# working.net
KiCad netlist of a schematic drawn in EAGLE
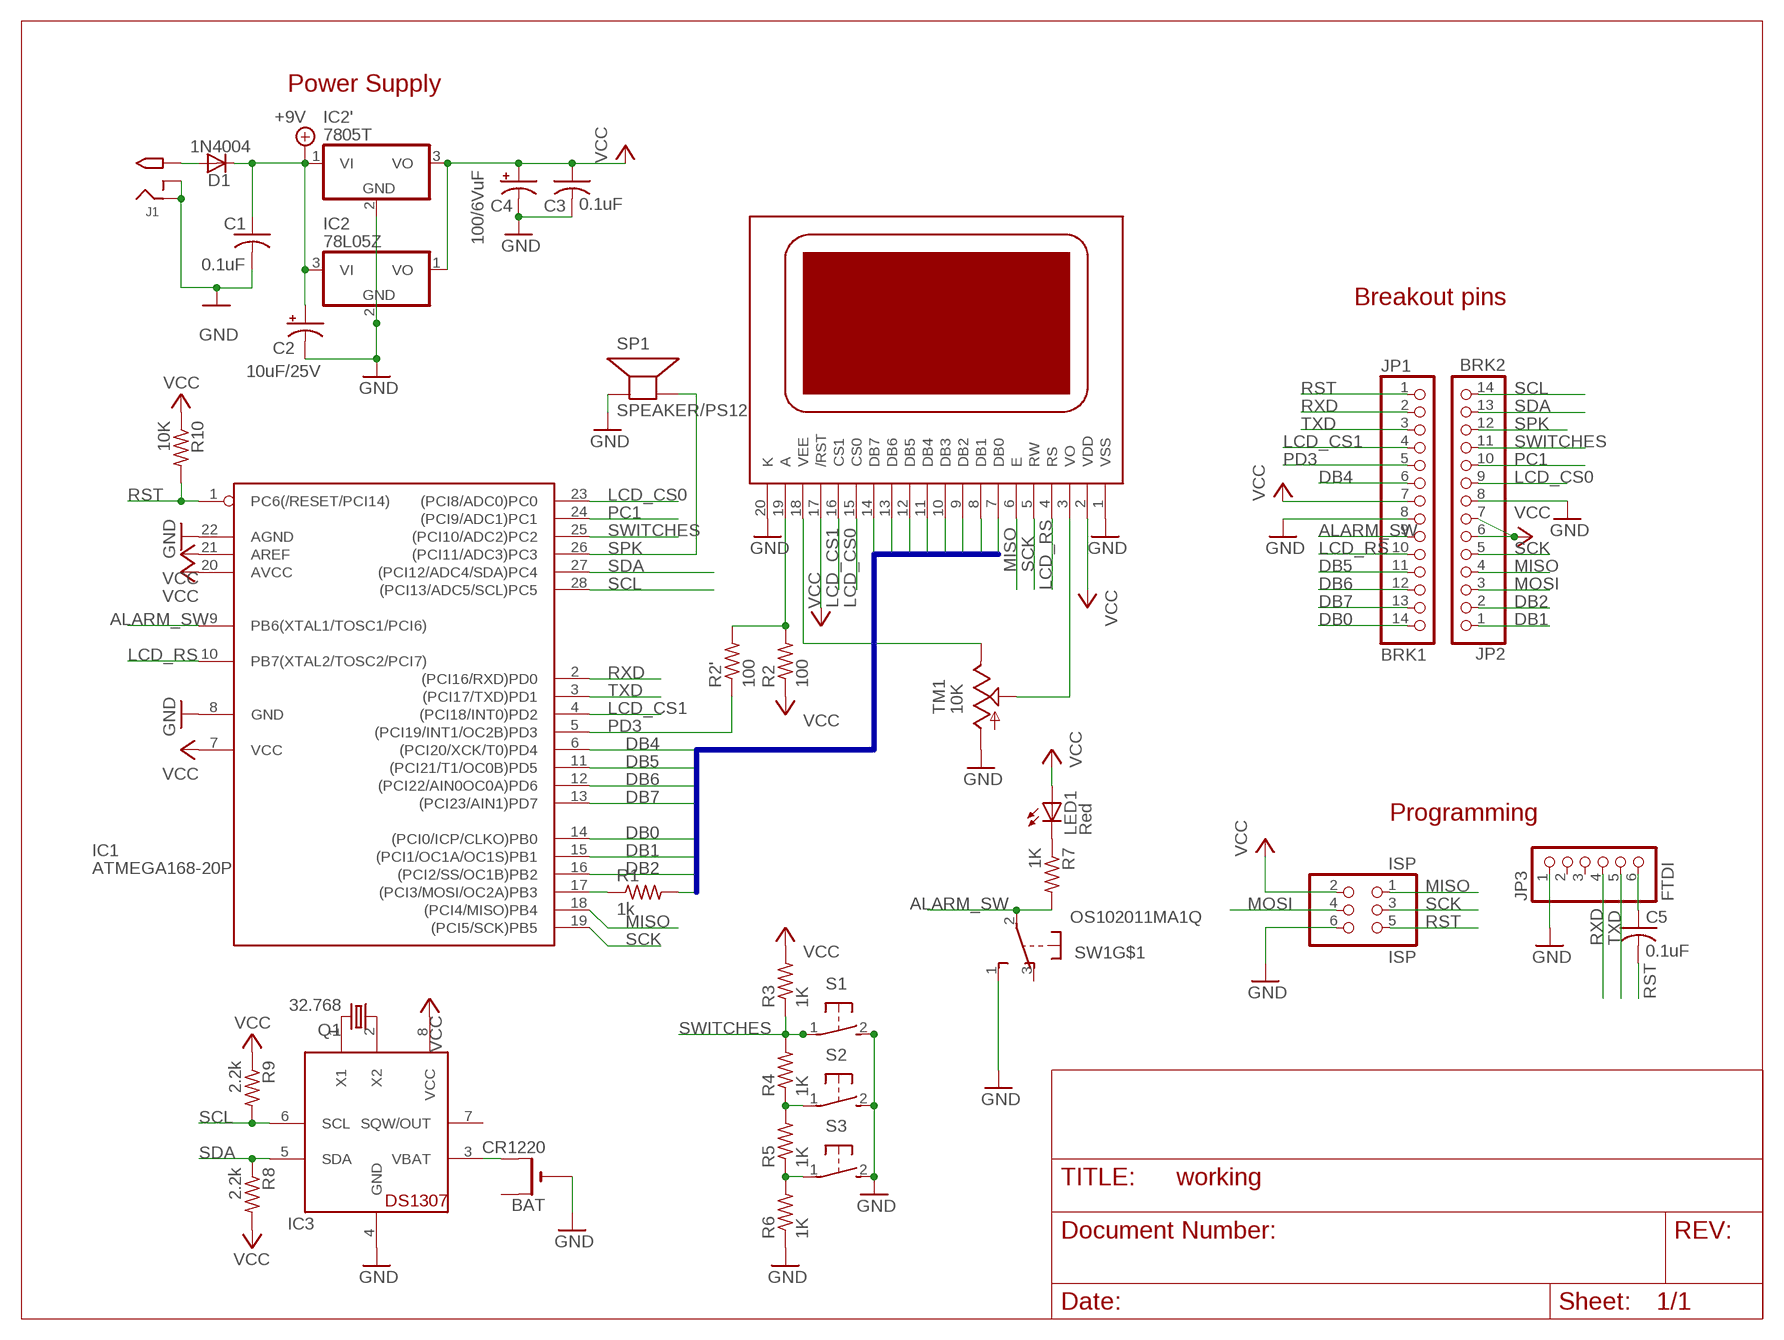
[diagram p0: schematic, sheet 1]

(export (version "E")
  (design (tool "Eeschema 10.0.6"))
  (components
    (comp (ref "BAT")
      (value "CR1220")
      (footprint "eagle-import:CR1220-THM")
      (libsource (lib "eagle-import") (part "CR1220THM"))
    )
    (comp (ref "C1")
      (value "0.1uF")
      (footprint "eagle-import:C025-025X050")
      (libsource (lib "eagle-import") (part "C-US025-025X050"))
    )
    (comp (ref "C2")
      (value "10uF/25V")
      (footprint "eagle-import:E2,5-6E")
      (libsource (lib "eagle-import") (part "CPOL-USE2,5-6E"))
    )
    (comp (ref "C3")
      (value "0.1uF")
      (footprint "eagle-import:C025-025X050")
      (libsource (lib "eagle-import") (part "C-US025-025X050"))
    )
    (comp (ref "C4")
      (value "100/6VuF")
      (footprint "eagle-import:E2,5-6E")
      (libsource (lib "eagle-import") (part "CPOL-USE2,5-6E"))
    )
    (comp (ref "C5")
      (value "0.1uF")
      (footprint "eagle-import:C025-025X050")
      (libsource (lib "eagle-import") (part "C-US025-025X050"))
    )
    (comp (ref "D1")
      (value "1N4004")
      (footprint "eagle-import:DO41-10")
      (libsource (lib "eagle-import") (part "1N4004"))
    )
    (comp (ref "IC1")
      (value "ATMEGA168-20P")
      (footprint "eagle-import:DIL28-3")
      (libsource (lib "eagle-import") (part "ATMEGA168P-20"))
    )
    (comp (ref "IC2")
      (value "78L05Z")
      (footprint "eagle-import:TO92")
      (libsource (lib "eagle-import") (part "linear-ez_78ZL05"))
    )
    (comp (ref "IC2'")
      (value "7805T")
      (footprint "eagle-import:TO220H")
      (libsource (lib "eagle-import") (part "78T05"))
    )
    (comp (ref "IC3")
      (value "DS1307")
      (footprint "eagle-import:DIL08")
      (libsource (lib "eagle-import") (part "DS1307"))
    )
    (comp (ref "ISP")
      (value "ISP")
      (footprint "eagle-import:2X03")
      (libsource (lib "eagle-import") (part "PINHD-2X3"))
    )
    (comp (ref "J1")
      (value "2.1MMJACK")
      (footprint "eagle-import:PJ-102A")
      (libsource (lib "eagle-import") (part "2.1MMJACK"))
    )
    (comp (ref "JP1")
      (value "BRK1")
      (footprint "eagle-import:1X14")
      (libsource (lib "eagle-import") (part "PINHD-1X14"))
    )
    (comp (ref "JP2")
      (value "BRK2")
      (footprint "eagle-import:1X14")
      (libsource (lib "eagle-import") (part "PINHD-1X14"))
    )
    (comp (ref "JP3")
      (value "FTDI")
      (footprint "eagle-import:1X06")
      (libsource (lib "eagle-import") (part "PINHD-1X6"))
    )
    (comp (ref "LED1")
      (value "Red")
      (footprint "eagle-import:LED3MM")
      (libsource (lib "eagle-import") (part "LED3MM"))
    )
    (comp (ref "Q1")
      (value "32.768")
      (footprint "eagle-import:TC38H")
      (libsource (lib "eagle-import") (part "CRYTALTC38H"))
    )
    (comp (ref "R1")
      (value "1k")
      (footprint "eagle-import:0207_10")
      (libsource (lib "eagle-import") (part "R-US_0207/10"))
    )
    (comp (ref "R2")
      (value "100")
      (footprint "eagle-import:0207_10")
      (libsource (lib "eagle-import") (part "R-US_0207/10"))
    )
    (comp (ref "R2'")
      (value "100")
      (footprint "eagle-import:0207_10")
      (libsource (lib "eagle-import") (part "R-US_0207/10"))
    )
    (comp (ref "R3")
      (value "1K")
      (footprint "eagle-import:0207_10")
      (libsource (lib "eagle-import") (part "R-US_0207/10"))
    )
    (comp (ref "R4")
      (value "1K")
      (footprint "eagle-import:0207_10")
      (libsource (lib "eagle-import") (part "R-US_0207/10"))
    )
    (comp (ref "R5")
      (value "1K")
      (footprint "eagle-import:0207_10")
      (libsource (lib "eagle-import") (part "R-US_0207/10"))
    )
    (comp (ref "R6")
      (value "1K")
      (footprint "eagle-import:0207_10")
      (libsource (lib "eagle-import") (part "R-US_0207/10"))
    )
    (comp (ref "R7")
      (value "1K")
      (footprint "eagle-import:0207_10")
      (libsource (lib "eagle-import") (part "R-US_0207/10"))
    )
    (comp (ref "R8")
      (value "2.2k")
      (footprint "eagle-import:0207_10")
      (libsource (lib "eagle-import") (part "R-US_0207/10"))
    )
    (comp (ref "R9")
      (value "2.2k")
      (footprint "eagle-import:0207_10")
      (libsource (lib "eagle-import") (part "R-US_0207/10"))
    )
    (comp (ref "R10")
      (value "10K")
      (footprint "eagle-import:0207_10")
      (libsource (lib "eagle-import") (part "R-US_0207/10"))
    )
    (comp (ref "S1")
      (value "31-XX")
      (footprint "eagle-import:B3F-31XX")
      (libsource (lib "eagle-import") (part "31-XX"))
    )
    (comp (ref "S2")
      (value "31-XX")
      (footprint "eagle-import:B3F-31XX")
      (libsource (lib "eagle-import") (part "31-XX"))
    )
    (comp (ref "S3")
      (value "31-XX")
      (footprint "eagle-import:B3F-31XX")
      (libsource (lib "eagle-import") (part "31-XX"))
    )
    (comp (ref "SP1")
      (value "SPEAKER/PS12")
      (footprint "eagle-import:PS12")
      (libsource (lib "eagle-import") (part "SPEAKER/PS12"))
    )
    (comp (ref "SW1")
      (value "OS102011MA1Q")
      (footprint "eagle-import:OS102011MA1Q")
      (libsource (lib "eagle-import") (part "OS102011MA1Q"))
    )
    (comp (ref "TM1")
      (value "10K")
      (footprint "eagle-import:CA6H")
      (libsource (lib "eagle-import") (part "TRIM_US-CA6H"))
    )
    (comp (ref "U$1")
      (value "TS12864A")
      (footprint "eagle-import:TS12864")
      (libsource (lib "eagle-import") (part "TS12864A"))
    )
  )
  (nets
    (net (code "1") (name "+9V") (class "Default")
      (node (ref "C1") (pin "1") (pinfunction "1_1") (pintype "passive"))
      (node (ref "C2") (pin "+") (pinfunction "+_+") (pintype "passive"))
      (node (ref "D1") (pin "C") (pinfunction "C_C") (pintype "passive"))
      (node (ref "IC2") (pin "3") (pinfunction "VI_3") (pintype "input"))
      (node (ref "IC2'") (pin "1") (pinfunction "VI_1") (pintype "input"))
    )
    (net (code "2") (name "/ALARM_SW") (class "Default")
      (node (ref "IC1") (pin "9") (pinfunction "PB6(XTAL1/TOSC1/PCI6)_9") (pintype "bidirectional"))
      (node (ref "JP1") (pin "9") (pinfunction "9_9") (pintype "passive"))
      (node (ref "R7") (pin "2") (pinfunction "2_2") (pintype "passive"))
      (node (ref "SW1") (pin "2") (pinfunction "P_2") (pintype "passive"))
    )
    (net (code "3") (name "/DB0") (class "Default")
      (node (ref "IC1") (pin "14") (pinfunction "(PCI0/ICP/CLKO)PB0_14") (pintype "bidirectional"))
      (node (ref "JP1") (pin "14") (pinfunction "14_14") (pintype "passive"))
      (node (ref "U$1") (pin "7") (pinfunction "DB0_7") (pintype "bidirectional"))
    )
    (net (code "4") (name "/DB1") (class "Default")
      (node (ref "IC1") (pin "15") (pinfunction "(PCI1/OC1A/OC1S)PB1_15") (pintype "bidirectional"))
      (node (ref "JP2") (pin "1") (pinfunction "1_1") (pintype "passive"))
      (node (ref "U$1") (pin "8") (pinfunction "DB1_8") (pintype "bidirectional"))
    )
    (net (code "5") (name "/DB2") (class "Default")
      (node (ref "IC1") (pin "16") (pinfunction "(PCI2/SS/OC1B)PB2_16") (pintype "bidirectional"))
      (node (ref "JP2") (pin "2") (pinfunction "2_2") (pintype "passive"))
      (node (ref "U$1") (pin "9") (pinfunction "DB2_9") (pintype "bidirectional"))
    )
    (net (code "6") (name "/DB3") (class "Default")
      (node (ref "R1") (pin "2") (pinfunction "2_2") (pintype "passive"))
      (node (ref "U$1") (pin "10") (pinfunction "DB3_10") (pintype "bidirectional"))
    )
    (net (code "7") (name "/DB4") (class "Default")
      (node (ref "IC1") (pin "6") (pinfunction "(PCI20/XCK/T0)PD4_6") (pintype "bidirectional"))
      (node (ref "JP1") (pin "6") (pinfunction "6_6") (pintype "passive"))
      (node (ref "U$1") (pin "11") (pinfunction "DB4_11") (pintype "bidirectional"))
    )
    (net (code "8") (name "/DB5") (class "Default")
      (node (ref "IC1") (pin "11") (pinfunction "(PCI21/T1/OC0B)PD5_11") (pintype "bidirectional"))
      (node (ref "JP1") (pin "11") (pinfunction "11_11") (pintype "passive"))
      (node (ref "U$1") (pin "12") (pinfunction "DB5_12") (pintype "bidirectional"))
    )
    (net (code "9") (name "/DB6") (class "Default")
      (node (ref "IC1") (pin "12") (pinfunction "(PCI22/AIN0OC0A)PD6_12") (pintype "bidirectional"))
      (node (ref "JP1") (pin "12") (pinfunction "12_12") (pintype "passive"))
      (node (ref "U$1") (pin "13") (pinfunction "DB6_13") (pintype "bidirectional"))
    )
    (net (code "10") (name "/DB7") (class "Default")
      (node (ref "IC1") (pin "13") (pinfunction "(PCI23/AIN1)PD7_13") (pintype "bidirectional"))
      (node (ref "JP1") (pin "13") (pinfunction "13_13") (pintype "passive"))
      (node (ref "U$1") (pin "14") (pinfunction "DB7_14") (pintype "bidirectional"))
    )
    (net (code "11") (name "/LCD_CS0") (class "Default")
      (node (ref "IC1") (pin "23") (pinfunction "(PCI8/ADC0)PC0_23") (pintype "bidirectional"))
      (node (ref "JP2") (pin "9") (pinfunction "9_9") (pintype "passive"))
      (node (ref "U$1") (pin "15") (pinfunction "CS0_15") (pintype "input"))
    )
    (net (code "12") (name "/LCD_CS1") (class "Default")
      (node (ref "IC1") (pin "4") (pinfunction "(PCI18/INT0)PD2_4") (pintype "bidirectional"))
      (node (ref "JP1") (pin "4") (pinfunction "4_4") (pintype "passive"))
      (node (ref "U$1") (pin "16") (pinfunction "CS1_16") (pintype "input"))
    )
    (net (code "13") (name "/LCD_RS") (class "Default")
      (node (ref "IC1") (pin "10") (pinfunction "PB7(XTAL2/TOSC2/PCI7)_10") (pintype "bidirectional"))
      (node (ref "JP1") (pin "10") (pinfunction "10_10") (pintype "passive"))
      (node (ref "U$1") (pin "4") (pinfunction "RS_4") (pintype "input"))
    )
    (net (code "14") (name "/MISO") (class "Default")
      (node (ref "IC1") (pin "18") (pinfunction "(PCI4/MISO)PB4_18") (pintype "bidirectional"))
      (node (ref "ISP") (pin "1") (pinfunction "1_1") (pintype "passive"))
      (node (ref "JP2") (pin "4") (pinfunction "4_4") (pintype "passive"))
      (node (ref "U$1") (pin "6") (pinfunction "E_6") (pintype "input"))
    )
    (net (code "15") (name "/MOSI") (class "Default")
      (node (ref "IC1") (pin "17") (pinfunction "(PCI3/MOSI/OC2A)PB3_17") (pintype "bidirectional"))
      (node (ref "ISP") (pin "4") (pinfunction "4_4") (pintype "passive"))
      (node (ref "JP2") (pin "3") (pinfunction "3_3") (pintype "passive"))
      (node (ref "R1") (pin "1") (pinfunction "1_1") (pintype "passive"))
    )
    (net (code "16") (name "/PC1") (class "Default")
      (node (ref "IC1") (pin "24") (pinfunction "(PCI9/ADC1)PC1_24") (pintype "bidirectional"))
      (node (ref "JP2") (pin "10") (pinfunction "10_10") (pintype "passive"))
    )
    (net (code "17") (name "/PD3") (class "Default")
      (node (ref "IC1") (pin "5") (pinfunction "(PCI19/INT1/OC2B)PD3_5") (pintype "bidirectional"))
      (node (ref "JP1") (pin "5") (pinfunction "5_5") (pintype "passive"))
      (node (ref "R2'") (pin "1") (pinfunction "1_1") (pintype "passive"))
    )
    (net (code "18") (name "/RST") (class "Default")
      (node (ref "C5") (pin "2") (pinfunction "2_2") (pintype "passive"))
      (node (ref "IC1") (pin "1") (pinfunction "PC6(/RESET/PCI14)_1") (pintype "bidirectional"))
      (node (ref "ISP") (pin "5") (pinfunction "5_5") (pintype "passive"))
      (node (ref "JP1") (pin "1") (pinfunction "1_1") (pintype "passive"))
      (node (ref "R10") (pin "2") (pinfunction "2_2") (pintype "passive"))
    )
    (net (code "19") (name "/RXD") (class "Default")
      (node (ref "IC1") (pin "2") (pinfunction "(PCI16/RXD)PD0_2") (pintype "bidirectional"))
      (node (ref "JP1") (pin "2") (pinfunction "2_2") (pintype "passive"))
      (node (ref "JP3") (pin "4") (pinfunction "4_4") (pintype "passive"))
    )
    (net (code "20") (name "/SCK") (class "Default")
      (node (ref "IC1") (pin "19") (pinfunction "(PCI5/SCK)PB5_19") (pintype "bidirectional"))
      (node (ref "ISP") (pin "3") (pinfunction "3_3") (pintype "passive"))
      (node (ref "JP2") (pin "5") (pinfunction "5_5") (pintype "passive"))
      (node (ref "U$1") (pin "5") (pinfunction "RW_5") (pintype "input"))
    )
    (net (code "21") (name "/SCL") (class "Default")
      (node (ref "IC1") (pin "28") (pinfunction "(PCI13/ADC5/SCL)PC5_28") (pintype "bidirectional"))
      (node (ref "IC3") (pin "6") (pinfunction "SCL_6") (pintype "bidirectional"))
      (node (ref "JP2") (pin "14") (pinfunction "14_14") (pintype "passive"))
      (node (ref "R9") (pin "2") (pinfunction "2_2") (pintype "passive"))
    )
    (net (code "22") (name "/SDA") (class "Default")
      (node (ref "IC1") (pin "27") (pinfunction "(PCI12/ADC4/SDA)PC4_27") (pintype "bidirectional"))
      (node (ref "IC3") (pin "5") (pinfunction "SDA_5") (pintype "bidirectional"))
      (node (ref "JP2") (pin "13") (pinfunction "13_13") (pintype "passive"))
      (node (ref "R8") (pin "1") (pinfunction "1_1") (pintype "passive"))
    )
    (net (code "23") (name "/SPK") (class "Default")
      (node (ref "IC1") (pin "26") (pinfunction "(PCI11/ADC3)PC3_26") (pintype "bidirectional"))
      (node (ref "JP2") (pin "12") (pinfunction "12_12") (pintype "passive"))
      (node (ref "SP1") (pin "P$2") (pinfunction "-_P$2") (pintype "passive"))
    )
    (net (code "24") (name "/SWITCHES") (class "Default")
      (node (ref "IC1") (pin "25") (pinfunction "(PCI10/ADC2)PC2_25") (pintype "bidirectional"))
      (node (ref "JP2") (pin "11") (pinfunction "11_11") (pintype "passive"))
      (node (ref "R3") (pin "1") (pinfunction "1_1") (pintype "passive"))
      (node (ref "R4") (pin "2") (pinfunction "2_2") (pintype "passive"))
      (node (ref "S1") (pin "1") (pinfunction "P_1") (pintype "passive"))
    )
    (net (code "25") (name "/TXD") (class "Default")
      (node (ref "IC1") (pin "3") (pinfunction "(PCI17/TXD)PD1_3") (pintype "bidirectional"))
      (node (ref "JP1") (pin "3") (pinfunction "3_3") (pintype "passive"))
      (node (ref "JP3") (pin "5") (pinfunction "5_5") (pintype "passive"))
    )
    (net (code "26") (name "GND") (class "Default")
      (node (ref "BAT") (pin "-") (pinfunction "-_-") (pintype "passive"))
      (node (ref "C1") (pin "2") (pinfunction "2_2") (pintype "passive"))
      (node (ref "C2") (pin "-") (pinfunction "-_-") (pintype "passive"))
      (node (ref "C3") (pin "2") (pinfunction "2_2") (pintype "passive"))
      (node (ref "C4") (pin "-") (pinfunction "-_-") (pintype "passive"))
      (node (ref "IC1") (pin "22") (pinfunction "AGND_22") (pintype "bidirectional"))
      (node (ref "IC1") (pin "8") (pinfunction "GND_8") (pintype "bidirectional"))
      (node (ref "IC2") (pin "2") (pinfunction "GND_2") (pintype "passive"))
      (node (ref "IC2'") (pin "2") (pinfunction "GND_2") (pintype "passive"))
      (node (ref "IC3") (pin "4") (pinfunction "GND_4") (pintype "power_in"))
      (node (ref "ISP") (pin "6") (pinfunction "6_6") (pintype "passive"))
      (node (ref "J1") (pin "RING") (pinfunction "RING_RING") (pintype "bidirectional"))
      (node (ref "J1") (pin "RING_SW") (pinfunction "RING_SW_RING_SW") (pintype "bidirectional"))
      (node (ref "JP1") (pin "8") (pinfunction "8_8") (pintype "passive"))
      (node (ref "JP2") (pin "8") (pinfunction "8_8") (pintype "passive"))
      (node (ref "JP3") (pin "1") (pinfunction "1_1") (pintype "passive"))
      (node (ref "R6") (pin "1") (pinfunction "1_1") (pintype "passive"))
      (node (ref "S1") (pin "2") (pinfunction "S_2") (pintype "passive"))
      (node (ref "S2") (pin "2") (pinfunction "S_2") (pintype "passive"))
      (node (ref "S3") (pin "2") (pinfunction "S_2") (pintype "passive"))
      (node (ref "SP1") (pin "P$1") (pinfunction "+_P$1") (pintype "passive"))
      (node (ref "SW1") (pin "1") (pinfunction "S_1") (pintype "passive"))
      (node (ref "TM1") (pin "A") (pinfunction "A_A") (pintype "passive"))
      (node (ref "U$1") (pin "1") (pinfunction "VSS_1") (pintype "power_in"))
      (node (ref "U$1") (pin "20") (pinfunction "K_20") (pintype "input"))
    )
    (net (code "27") (name "Net-(BAT-+1)") (class "Default")
      (node (ref "BAT") (pin "+2") (pinfunction "+1_+2") (pintype "passive"))
      (node (ref "IC3") (pin "3") (pinfunction "VBAT_3") (pintype "power_in"))
    )
    (net (code "28") (name "Net-(C5-Pad1)") (class "Default")
      (node (ref "C5") (pin "1") (pinfunction "1_1") (pintype "passive"))
      (node (ref "JP3") (pin "6") (pinfunction "6_6") (pintype "passive"))
    )
    (net (code "29") (name "Net-(D1-PadA)") (class "Default")
      (node (ref "D1") (pin "A") (pinfunction "A_A") (pintype "passive"))
      (node (ref "J1") (pin "TIP") (pinfunction "TIP_TIP") (pintype "bidirectional"))
    )
    (net (code "30") (name "Net-(IC3-X1)") (class "Default")
      (node (ref "IC3") (pin "1") (pinfunction "X1_1") (pintype "passive"))
      (node (ref "Q1") (pin "2") (pinfunction "2_2") (pintype "passive"))
    )
    (net (code "31") (name "Net-(IC3-X2)") (class "Default")
      (node (ref "IC3") (pin "2") (pinfunction "X2_2") (pintype "passive"))
      (node (ref "Q1") (pin "1") (pinfunction "1_1") (pintype "passive"))
    )
    (net (code "32") (name "Net-(LED1-C)") (class "Default")
      (node (ref "LED1") (pin "K") (pinfunction "C_K") (pintype "passive"))
      (node (ref "R7") (pin "1") (pinfunction "1_1") (pintype "passive"))
    )
    (net (code "33") (name "Net-(S2-P)") (class "Default")
      (node (ref "R4") (pin "1") (pinfunction "1_1") (pintype "passive"))
      (node (ref "R5") (pin "2") (pinfunction "2_2") (pintype "passive"))
      (node (ref "S2") (pin "1") (pinfunction "P_1") (pintype "passive"))
    )
    (net (code "34") (name "Net-(S3-P)") (class "Default")
      (node (ref "R5") (pin "1") (pinfunction "1_1") (pintype "passive"))
      (node (ref "R6") (pin "2") (pinfunction "2_2") (pintype "passive"))
      (node (ref "S3") (pin "1") (pinfunction "P_1") (pintype "passive"))
    )
    (net (code "35") (name "Net-(U$1-A)") (class "Default")
      (node (ref "R2") (pin "2") (pinfunction "2_2") (pintype "passive"))
      (node (ref "R2'") (pin "2") (pinfunction "2_2") (pintype "passive"))
      (node (ref "U$1") (pin "19") (pinfunction "A_19") (pintype "power_in"))
    )
    (net (code "36") (name "Net-(U$1-VEE)") (class "Default")
      (node (ref "TM1") (pin "E") (pinfunction "E_E") (pintype "passive"))
      (node (ref "U$1") (pin "18") (pinfunction "VEE_18") (pintype "power_in"))
    )
    (net (code "37") (name "Net-(U$1-VO)") (class "Default")
      (node (ref "TM1") (pin "S") (pinfunction "S_S") (pintype "passive"))
      (node (ref "U$1") (pin "3") (pinfunction "VO_3") (pintype "input"))
    )
    (net (code "38") (name "VCC") (class "Default")
      (node (ref "C3") (pin "1") (pinfunction "1_1") (pintype "passive"))
      (node (ref "C4") (pin "+") (pinfunction "+_+") (pintype "passive"))
      (node (ref "IC1") (pin "20") (pinfunction "AVCC_20") (pintype "bidirectional"))
      (node (ref "IC1") (pin "21") (pinfunction "AREF_21") (pintype "bidirectional"))
      (node (ref "IC1") (pin "7") (pinfunction "VCC_7") (pintype "bidirectional"))
      (node (ref "IC2") (pin "1") (pinfunction "VO_1") (pintype "passive"))
      (node (ref "IC2'") (pin "3") (pinfunction "VO_3") (pintype "passive"))
      (node (ref "IC3") (pin "8") (pinfunction "VCC_8") (pintype "power_in"))
      (node (ref "ISP") (pin "2") (pinfunction "2_2") (pintype "passive"))
      (node (ref "JP1") (pin "7") (pinfunction "7_7") (pintype "passive"))
      (node (ref "JP2") (pin "6") (pinfunction "6_6") (pintype "passive"))
      (node (ref "JP2") (pin "7") (pinfunction "7_7") (pintype "passive"))
      (node (ref "LED1") (pin "A") (pinfunction "A_A") (pintype "passive"))
      (node (ref "R10") (pin "1") (pinfunction "1_1") (pintype "passive"))
      (node (ref "R2") (pin "1") (pinfunction "1_1") (pintype "passive"))
      (node (ref "R3") (pin "2") (pinfunction "2_2") (pintype "passive"))
      (node (ref "R8") (pin "2") (pinfunction "2_2") (pintype "passive"))
      (node (ref "R9") (pin "1") (pinfunction "1_1") (pintype "passive"))
      (node (ref "U$1") (pin "17") (pinfunction "/RST_17") (pintype "input"))
      (node (ref "U$1") (pin "2") (pinfunction "VDD_2") (pintype "power_in"))
    )
    (net (code "39") (name "unconnected-(BAT-+-Pad+1)") (class "Default")
      (node (ref "BAT") (pin "+1") (pinfunction "+_+1") (pintype "passive"))
    )
    (net (code "40") (name "unconnected-(IC3-SQW{slash}OUT-Pad7)") (class "Default")
      (node (ref "IC3") (pin "7") (pinfunction "SQW/OUT_7") (pintype "bidirectional"))
    )
    (net (code "41") (name "unconnected-(JP3-Pad2)") (class "Default")
      (node (ref "JP3") (pin "2") (pinfunction "2_2") (pintype "passive"))
    )
    (net (code "42") (name "unconnected-(JP3-Pad3)") (class "Default")
      (node (ref "JP3") (pin "3") (pinfunction "3_3") (pintype "passive"))
    )
    (net (code "43") (name "unconnected-(SW1A-O-Pad3)") (class "Default")
      (node (ref "SW1") (pin "3") (pinfunction "O_3") (pintype "passive"))
    )
  )
)
